# Basisboard_REV0100.net
KiCad netlist of a schematic drawn in EAGLE
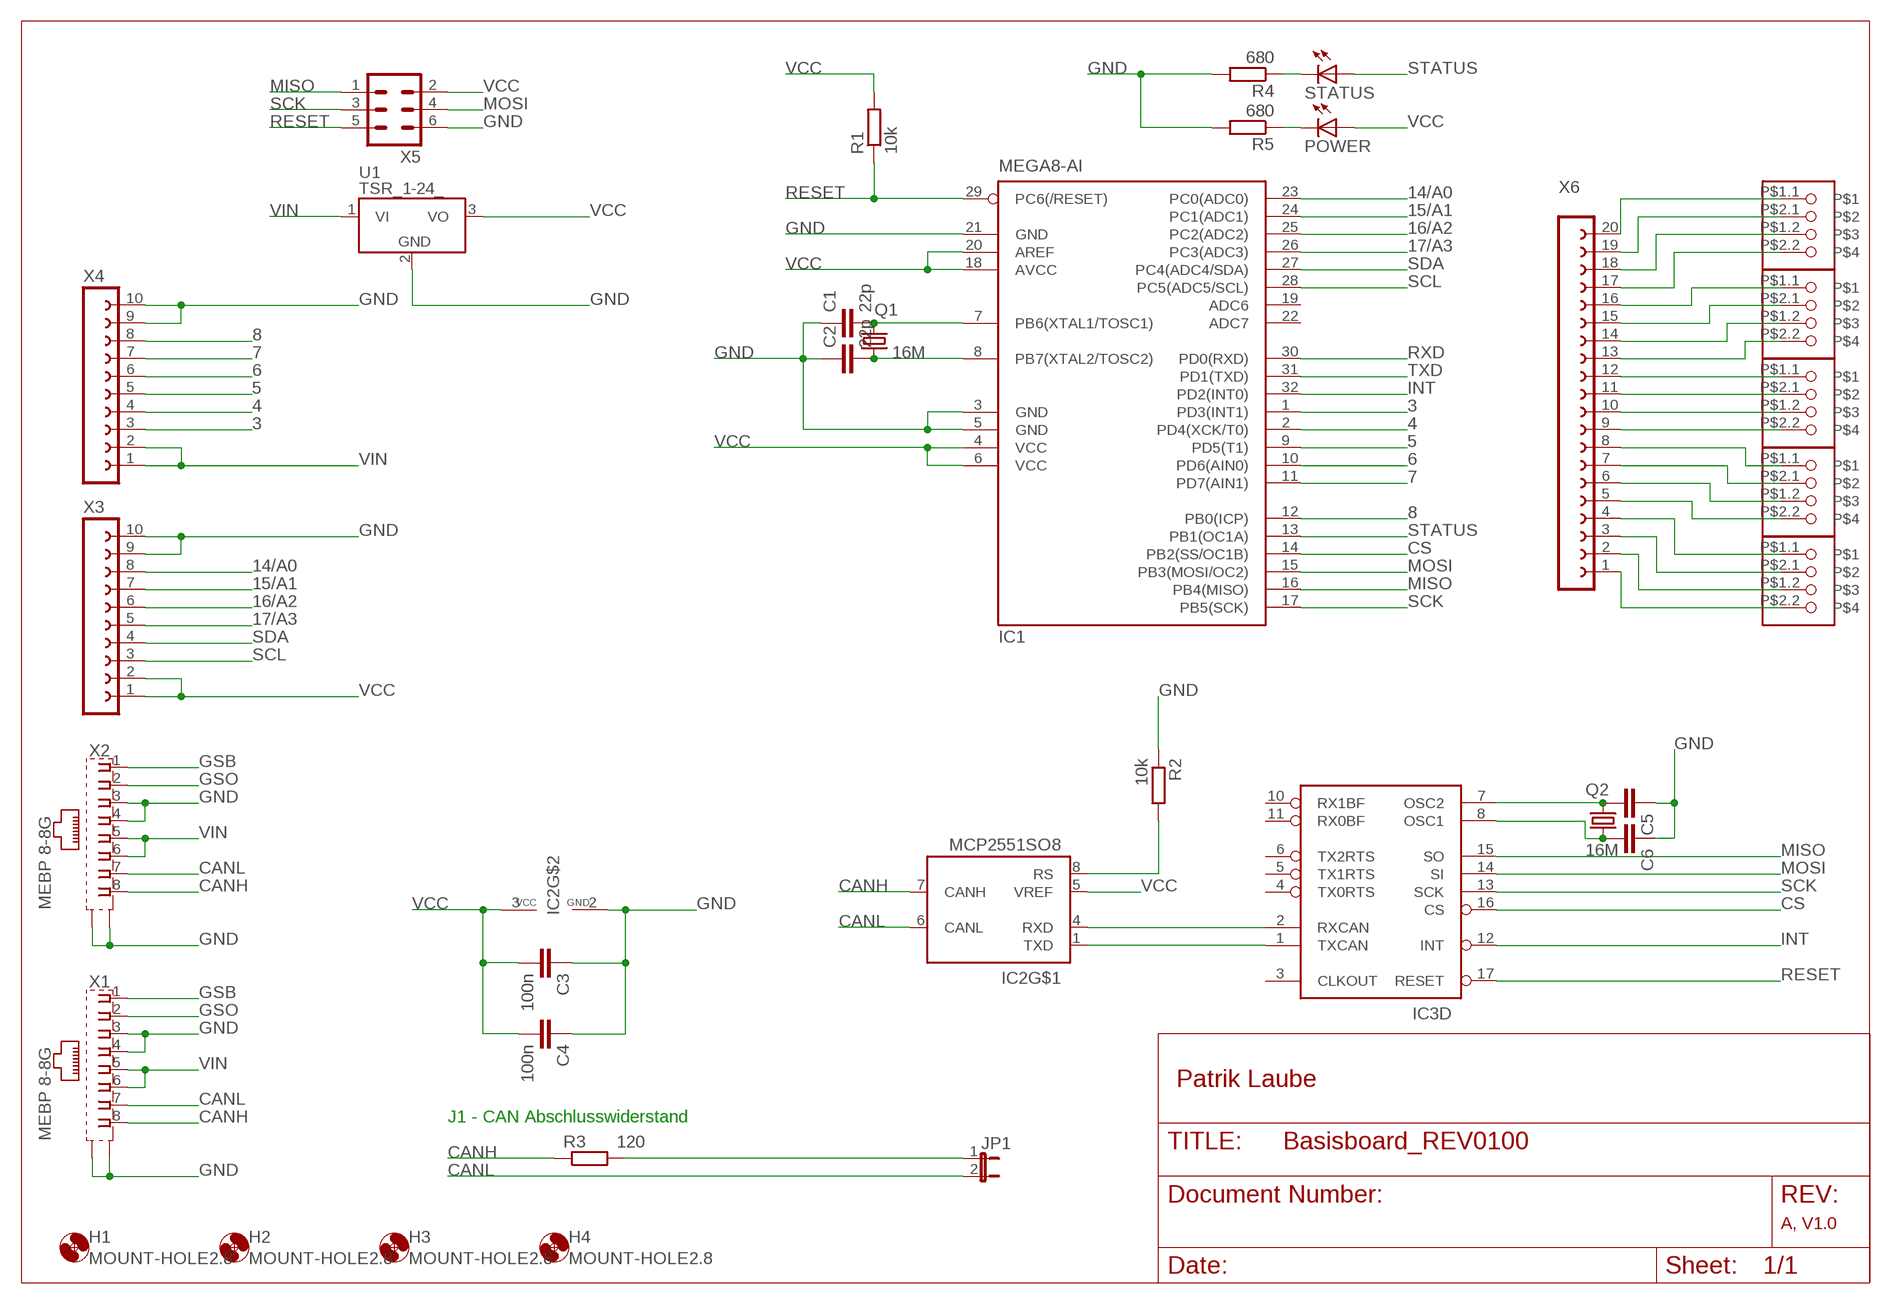
[diagram p0: schematic, sheet 1]

(export (version "E")
  (design (tool "Eeschema 10.0.6"))
  (components
    (comp (ref "C1")
      (value "22p")
      (footprint "eagle-import:C1206")
      (libsource (lib "eagle-import") (part "C-EUC1206"))
    )
    (comp (ref "C2")
      (value "22p")
      (footprint "eagle-import:C1206")
      (libsource (lib "eagle-import") (part "C-EUC1206"))
    )
    (comp (ref "C3")
      (value "100n")
      (footprint "eagle-import:C1206")
      (libsource (lib "eagle-import") (part "C-EUC1206"))
    )
    (comp (ref "C4")
      (value "100n")
      (footprint "eagle-import:C1206")
      (libsource (lib "eagle-import") (part "C-EUC1206"))
    )
    (comp (ref "C5")
      (value "C-EUC1206")
      (footprint "eagle-import:C1206")
      (libsource (lib "eagle-import") (part "C-EUC1206"))
    )
    (comp (ref "C6")
      (value "C-EUC1206")
      (footprint "eagle-import:C1206")
      (libsource (lib "eagle-import") (part "C-EUC1206"))
    )
    (comp (ref "H1")
      (value "MOUNT-HOLE2.8")
      (footprint "eagle-import:2,8")
      (libsource (lib "eagle-import") (part "MOUNT-HOLE2.8"))
    )
    (comp (ref "H2")
      (value "MOUNT-HOLE2.8")
      (footprint "eagle-import:2,8")
      (libsource (lib "eagle-import") (part "MOUNT-HOLE2.8"))
    )
    (comp (ref "H3")
      (value "MOUNT-HOLE2.8")
      (footprint "eagle-import:2,8")
      (libsource (lib "eagle-import") (part "MOUNT-HOLE2.8"))
    )
    (comp (ref "H4")
      (value "MOUNT-HOLE2.8")
      (footprint "eagle-import:2,8")
      (libsource (lib "eagle-import") (part "MOUNT-HOLE2.8"))
    )
    (comp (ref "IC1")
      (value "MEGA8-AI")
      (footprint "eagle-import:TQFP32-08")
      (fields (field (name "MPN") "ATMEGA8-16AU"))
      (libsource (lib "eagle-import") (part "MEGA8-AI"))
    )
    (comp (ref "IC2")
      (value "MCP2551SO8")
      (footprint "eagle-import:SO08")
      (libsource (lib "eagle-import") (part "MCP2551SO8"))
    )
    (comp (ref "IC3")
      (value "MCP2515SO")
      (footprint "eagle-import:SO-18W")
      (libsource (lib "eagle-import") (part "MCP2515SO"))
    )
    (comp (ref "JP1")
      (value "JP1E")
      (footprint "eagle-import:JP1")
      (libsource (lib "eagle-import") (part "JP1E"))
    )
    (comp (ref "POWER")
      (value "LEDCHIPLED_1206")
      (footprint "eagle-import:CHIPLED_1206")
      (libsource (lib "eagle-import") (part "LEDCHIPLED_1206"))
    )
    (comp (ref "Q1")
      (value "16M")
      (footprint "eagle-import:HC49_S")
      (libsource (lib "eagle-import") (part "CRYSTALHC49S"))
    )
    (comp (ref "Q2")
      (value "16M")
      (footprint "eagle-import:HC49_S")
      (libsource (lib "eagle-import") (part "CRYSTALHC49S"))
    )
    (comp (ref "R1")
      (value "10k")
      (footprint "eagle-import:R1206")
      (libsource (lib "eagle-import") (part "R-EU_R1206"))
    )
    (comp (ref "R2")
      (value "10k")
      (footprint "eagle-import:R1206")
      (libsource (lib "eagle-import") (part "R-EU_R1206"))
    )
    (comp (ref "R3")
      (value "120")
      (footprint "eagle-import:R1206")
      (libsource (lib "eagle-import") (part "rcl_334_R-EU_R1206"))
    )
    (comp (ref "R4")
      (value "680")
      (footprint "eagle-import:R1206")
      (libsource (lib "eagle-import") (part "R-EU_R1206"))
    )
    (comp (ref "R5")
      (value "680")
      (footprint "eagle-import:R1206")
      (libsource (lib "eagle-import") (part "R-EU_R1206"))
    )
    (comp (ref "STATUS")
      (value "LEDCHIPLED_1206")
      (footprint "eagle-import:CHIPLED_1206")
      (libsource (lib "eagle-import") (part "LEDCHIPLED_1206"))
    )
    (comp (ref "U$4")
      (value "AKL093-06")
      (footprint "eagle-import:AKL093-06")
      (libsource (lib "eagle-import") (part "AKL093-06"))
    )
    (comp (ref "U$5")
      (value "AKL093-06")
      (footprint "eagle-import:AKL093-06")
      (libsource (lib "eagle-import") (part "AKL093-06"))
    )
    (comp (ref "U$6")
      (value "AKL093-06")
      (footprint "eagle-import:AKL093-06")
      (libsource (lib "eagle-import") (part "AKL093-06"))
    )
    (comp (ref "U$7")
      (value "AKL093-06")
      (footprint "eagle-import:AKL093-06")
      (libsource (lib "eagle-import") (part "AKL093-06"))
    )
    (comp (ref "U$8")
      (value "AKL093-06")
      (footprint "eagle-import:AKL093-06")
      (libsource (lib "eagle-import") (part "AKL093-06"))
    )
    (comp (ref "U1")
      (value "TSR_1-24_")
      (footprint "eagle-import:TSR-1")
      (libsource (lib "eagle-import") (part "TSR_1-24_"))
    )
    (comp (ref "X1")
      (value "MEBP 8-8G")
      (footprint "eagle-import:XRJF-01A-0-D2A-010")
      (libsource (lib "eagle-import") (part "XRJFMEBP-8-8G-01A-0-D22-020"))
    )
    (comp (ref "X2")
      (value "MEBP 8-8G")
      (footprint "eagle-import:XRJF-01A-0-D2A-010")
      (libsource (lib "eagle-import") (part "XRJFMEBP-8-8G-01A-0-D22-020"))
    )
    (comp (ref "X3")
      (value "FE10-1")
      (footprint "eagle-import:FE10")
      (libsource (lib "eagle-import") (part "FE10-1"))
    )
    (comp (ref "X4")
      (value "FE10-1")
      (footprint "eagle-import:FE10")
      (libsource (lib "eagle-import") (part "FE10-1"))
    )
    (comp (ref "X5")
      (value "MA03-2")
      (footprint "eagle-import:MA03-2")
      (libsource (lib "eagle-import") (part "MA03-2"))
    )
    (comp (ref "X6")
      (value "FE20-1")
      (footprint "eagle-import:FE20")
      (libsource (lib "eagle-import") (part "FE20-1"))
    )
  )
  (nets
    (net (code "1") (name "/3") (class "Default")
      (node (ref "IC1") (pin "1") (pinfunction "PD3(INT1)_1") (pintype "bidirectional"))
      (node (ref "X4") (pin "3") (pinfunction "3_3") (pintype "passive"))
    )
    (net (code "2") (name "/4") (class "Default")
      (node (ref "IC1") (pin "2") (pinfunction "PD4(XCK/T0)_2") (pintype "bidirectional"))
      (node (ref "X4") (pin "4") (pinfunction "4_4") (pintype "passive"))
    )
    (net (code "3") (name "/5") (class "Default")
      (node (ref "IC1") (pin "9") (pinfunction "PD5(T1)_9") (pintype "bidirectional"))
      (node (ref "X4") (pin "5") (pinfunction "5_5") (pintype "passive"))
    )
    (net (code "4") (name "/6") (class "Default")
      (node (ref "IC1") (pin "10") (pinfunction "PD6(AIN0)_10") (pintype "bidirectional"))
      (node (ref "X4") (pin "6") (pinfunction "6_6") (pintype "passive"))
    )
    (net (code "5") (name "/7") (class "Default")
      (node (ref "IC1") (pin "11") (pinfunction "PD7(AIN1)_11") (pintype "bidirectional"))
      (node (ref "X4") (pin "7") (pinfunction "7_7") (pintype "passive"))
    )
    (net (code "6") (name "/8") (class "Default")
      (node (ref "IC1") (pin "12") (pinfunction "PB0(ICP)_12") (pintype "bidirectional"))
      (node (ref "X4") (pin "8") (pinfunction "8_8") (pintype "passive"))
    )
    (net (code "7") (name "/14{slash}A0") (class "Default")
      (node (ref "IC1") (pin "23") (pinfunction "PC0(ADC0)_23") (pintype "bidirectional"))
      (node (ref "X3") (pin "8") (pinfunction "8_8") (pintype "passive"))
    )
    (net (code "8") (name "/15{slash}A1") (class "Default")
      (node (ref "IC1") (pin "24") (pinfunction "PC1(ADC1)_24") (pintype "bidirectional"))
      (node (ref "X3") (pin "7") (pinfunction "7_7") (pintype "passive"))
    )
    (net (code "9") (name "/16{slash}A2") (class "Default")
      (node (ref "IC1") (pin "25") (pinfunction "PC2(ADC2)_25") (pintype "bidirectional"))
      (node (ref "X3") (pin "6") (pinfunction "6_6") (pintype "passive"))
    )
    (net (code "10") (name "/17{slash}A3") (class "Default")
      (node (ref "IC1") (pin "26") (pinfunction "PC3(ADC3)_26") (pintype "bidirectional"))
      (node (ref "X3") (pin "5") (pinfunction "5_5") (pintype "passive"))
    )
    (net (code "11") (name "/CANH") (class "Default")
      (node (ref "IC2") (pin "7") (pinfunction "CANH_7") (pintype "bidirectional"))
      (node (ref "R3") (pin "1") (pinfunction "1_1") (pintype "passive"))
      (node (ref "X1") (pin "8") (pinfunction "8_8") (pintype "passive"))
      (node (ref "X2") (pin "8") (pinfunction "8_8") (pintype "passive"))
    )
    (net (code "12") (name "/CANL") (class "Default")
      (node (ref "IC2") (pin "6") (pinfunction "CANL_6") (pintype "bidirectional"))
      (node (ref "JP1") (pin "2") (pinfunction "2_2") (pintype "passive"))
      (node (ref "X1") (pin "7") (pinfunction "7_7") (pintype "passive"))
      (node (ref "X2") (pin "7") (pinfunction "7_7") (pintype "passive"))
    )
    (net (code "13") (name "/CS") (class "Default")
      (node (ref "IC1") (pin "14") (pinfunction "PB2(SS/OC1B)_14") (pintype "bidirectional"))
      (node (ref "IC3") (pin "16") (pinfunction "CS_16") (pintype "input"))
    )
    (net (code "14") (name "/GND") (class "Default")
      (node (ref "C1") (pin "1") (pinfunction "1_1") (pintype "passive"))
      (node (ref "C2") (pin "1") (pinfunction "1_1") (pintype "passive"))
      (node (ref "C3") (pin "1") (pinfunction "1_1") (pintype "passive"))
      (node (ref "C4") (pin "1") (pinfunction "1_1") (pintype "passive"))
      (node (ref "C5") (pin "1") (pinfunction "1_1") (pintype "passive"))
      (node (ref "C6") (pin "1") (pinfunction "1_1") (pintype "passive"))
      (node (ref "IC1") (pin "21") (pinfunction "GND_21") (pintype "power_in"))
      (node (ref "IC1") (pin "3") (pinfunction "GND_3") (pintype "power_in"))
      (node (ref "IC1") (pin "5") (pinfunction "GND_5") (pintype "power_in"))
      (node (ref "IC2") (pin "2") (pinfunction "GND_2") (pintype "power_in"))
      (node (ref "R2") (pin "1") (pinfunction "1_1") (pintype "passive"))
      (node (ref "R4") (pin "2") (pinfunction "2_2") (pintype "passive"))
      (node (ref "R5") (pin "2") (pinfunction "2_2") (pintype "passive"))
      (node (ref "U1") (pin "2") (pinfunction "GND_2") (pintype "power_in"))
      (node (ref "X1") (pin "3") (pinfunction "3_3") (pintype "passive"))
      (node (ref "X1") (pin "4") (pinfunction "4_4") (pintype "passive"))
      (node (ref "X1") (pin "S1") (pinfunction "S_S1") (pintype "passive"))
      (node (ref "X1") (pin "S2") (pinfunction "S_S2") (pintype "passive"))
      (node (ref "X2") (pin "3") (pinfunction "3_3") (pintype "passive"))
      (node (ref "X2") (pin "4") (pinfunction "4_4") (pintype "passive"))
      (node (ref "X2") (pin "S1") (pinfunction "S_S1") (pintype "passive"))
      (node (ref "X2") (pin "S2") (pinfunction "S_S2") (pintype "passive"))
      (node (ref "X3") (pin "10") (pinfunction "10_10") (pintype "passive"))
      (node (ref "X3") (pin "9") (pinfunction "9_9") (pintype "passive"))
      (node (ref "X4") (pin "10") (pinfunction "10_10") (pintype "passive"))
      (node (ref "X4") (pin "9") (pinfunction "9_9") (pintype "passive"))
      (node (ref "X5") (pin "6") (pinfunction "6_6") (pintype "passive"))
    )
    (net (code "15") (name "/GSB") (class "Default")
      (node (ref "X1") (pin "1") (pinfunction "1_1") (pintype "passive"))
      (node (ref "X2") (pin "1") (pinfunction "1_1") (pintype "passive"))
    )
    (net (code "16") (name "/GSO") (class "Default")
      (node (ref "X1") (pin "2") (pinfunction "2_2") (pintype "passive"))
      (node (ref "X2") (pin "2") (pinfunction "2_2") (pintype "passive"))
    )
    (net (code "17") (name "/INT") (class "Default")
      (node (ref "IC1") (pin "32") (pinfunction "PD2(INT0)_32") (pintype "bidirectional"))
      (node (ref "IC3") (pin "12") (pinfunction "INT_12") (pintype "output"))
    )
    (net (code "18") (name "/MISO") (class "Default")
      (node (ref "IC1") (pin "16") (pinfunction "PB4(MISO)_16") (pintype "bidirectional"))
      (node (ref "IC3") (pin "15") (pinfunction "SO_15") (pintype "output"))
      (node (ref "X5") (pin "1") (pinfunction "1_1") (pintype "passive"))
    )
    (net (code "19") (name "/MOSI") (class "Default")
      (node (ref "IC1") (pin "15") (pinfunction "PB3(MOSI/OC2)_15") (pintype "bidirectional"))
      (node (ref "IC3") (pin "14") (pinfunction "SI_14") (pintype "input"))
      (node (ref "X5") (pin "4") (pinfunction "4_4") (pintype "passive"))
    )
    (net (code "20") (name "/RESET") (class "Default")
      (node (ref "IC1") (pin "29") (pinfunction "PC6(/RESET)_29") (pintype "bidirectional"))
      (node (ref "IC3") (pin "17") (pinfunction "RESET_17") (pintype "input"))
      (node (ref "R1") (pin "1") (pinfunction "1_1") (pintype "passive"))
      (node (ref "X5") (pin "5") (pinfunction "5_5") (pintype "passive"))
    )
    (net (code "21") (name "/RXD") (class "Default")
      (node (ref "IC1") (pin "30") (pinfunction "PD0(RXD)_30") (pintype "bidirectional"))
    )
    (net (code "22") (name "/SCK") (class "Default")
      (node (ref "IC1") (pin "17") (pinfunction "PB5(SCK)_17") (pintype "bidirectional"))
      (node (ref "IC3") (pin "13") (pinfunction "SCK_13") (pintype "input"))
      (node (ref "X5") (pin "3") (pinfunction "3_3") (pintype "passive"))
    )
    (net (code "23") (name "/SCL") (class "Default")
      (node (ref "IC1") (pin "28") (pinfunction "PC5(ADC5/SCL)_28") (pintype "bidirectional"))
      (node (ref "X3") (pin "3") (pinfunction "3_3") (pintype "passive"))
    )
    (net (code "24") (name "/SDA") (class "Default")
      (node (ref "IC1") (pin "27") (pinfunction "PC4(ADC4/SDA)_27") (pintype "bidirectional"))
      (node (ref "X3") (pin "4") (pinfunction "4_4") (pintype "passive"))
    )
    (net (code "25") (name "/STATUS") (class "Default")
      (node (ref "IC1") (pin "13") (pinfunction "PB1(OC1A)_13") (pintype "bidirectional"))
      (node (ref "STATUS") (pin "A") (pinfunction "A_A") (pintype "passive"))
    )
    (net (code "26") (name "/TXD") (class "Default")
      (node (ref "IC1") (pin "31") (pinfunction "PD1(TXD)_31") (pintype "bidirectional"))
    )
    (net (code "27") (name "/VCC") (class "Default")
      (node (ref "C3") (pin "2") (pinfunction "2_2") (pintype "passive"))
      (node (ref "C4") (pin "2") (pinfunction "2_2") (pintype "passive"))
      (node (ref "IC1") (pin "18") (pinfunction "AVCC_18") (pintype "power_in"))
      (node (ref "IC1") (pin "20") (pinfunction "AREF_20") (pintype "passive"))
      (node (ref "IC1") (pin "4") (pinfunction "VCC_4") (pintype "power_in"))
      (node (ref "IC1") (pin "6") (pinfunction "VCC_6") (pintype "power_in"))
      (node (ref "IC2") (pin "3") (pinfunction "VCC_3") (pintype "power_in"))
      (node (ref "IC2") (pin "5") (pinfunction "VREF_5") (pintype "bidirectional"))
      (node (ref "POWER") (pin "A") (pinfunction "A_A") (pintype "passive"))
      (node (ref "R1") (pin "2") (pinfunction "2_2") (pintype "passive"))
      (node (ref "U1") (pin "3") (pinfunction "VO_3") (pintype "power_in"))
      (node (ref "X3") (pin "1") (pinfunction "1_1") (pintype "passive"))
      (node (ref "X3") (pin "2") (pinfunction "2_2") (pintype "passive"))
      (node (ref "X5") (pin "2") (pinfunction "2_2") (pintype "passive"))
    )
    (net (code "28") (name "/VIN") (class "Default")
      (node (ref "U1") (pin "1") (pinfunction "VI_1") (pintype "power_in"))
      (node (ref "X1") (pin "5") (pinfunction "5_5") (pintype "passive"))
      (node (ref "X1") (pin "6") (pinfunction "6_6") (pintype "passive"))
      (node (ref "X2") (pin "5") (pinfunction "5_5") (pintype "passive"))
      (node (ref "X2") (pin "6") (pinfunction "6_6") (pintype "passive"))
      (node (ref "X4") (pin "1") (pinfunction "1_1") (pintype "passive"))
      (node (ref "X4") (pin "2") (pinfunction "2_2") (pintype "passive"))
    )
    (net (code "29") (name "Net-(IC1-PB6(XTAL1{slash}TOSC1))") (class "Default")
      (node (ref "C1") (pin "2") (pinfunction "2_2") (pintype "passive"))
      (node (ref "IC1") (pin "7") (pinfunction "PB6(XTAL1/TOSC1)_7") (pintype "bidirectional"))
      (node (ref "Q1") (pin "2") (pinfunction "2_2") (pintype "passive"))
    )
    (net (code "30") (name "Net-(IC1-PB7(XTAL2{slash}TOSC2))") (class "Default")
      (node (ref "C2") (pin "2") (pinfunction "2_2") (pintype "passive"))
      (node (ref "IC1") (pin "8") (pinfunction "PB7(XTAL2/TOSC2)_8") (pintype "bidirectional"))
      (node (ref "Q1") (pin "1") (pinfunction "1_1") (pintype "passive"))
    )
    (net (code "31") (name "Net-(IC2A-RS)") (class "Default")
      (node (ref "IC2") (pin "8") (pinfunction "RS_8") (pintype "bidirectional"))
      (node (ref "R2") (pin "2") (pinfunction "2_2") (pintype "passive"))
    )
    (net (code "32") (name "Net-(IC2A-RXD)") (class "Default")
      (node (ref "IC2") (pin "4") (pinfunction "RXD_4") (pintype "bidirectional"))
      (node (ref "IC3") (pin "2") (pinfunction "RXCAN_2") (pintype "input"))
    )
    (net (code "33") (name "Net-(IC2A-TXD)") (class "Default")
      (node (ref "IC2") (pin "1") (pinfunction "TXD_1") (pintype "bidirectional"))
      (node (ref "IC3") (pin "1") (pinfunction "TXCAN_1") (pintype "output"))
    )
    (net (code "34") (name "Net-(IC3A-OSC1)") (class "Default")
      (node (ref "C6") (pin "2") (pinfunction "2_2") (pintype "passive"))
      (node (ref "IC3") (pin "8") (pinfunction "OSC1_8") (pintype "input"))
      (node (ref "Q2") (pin "2") (pinfunction "2_2") (pintype "passive"))
    )
    (net (code "35") (name "Net-(IC3A-OSC2)") (class "Default")
      (node (ref "C5") (pin "2") (pinfunction "2_2") (pintype "passive"))
      (node (ref "IC3") (pin "7") (pinfunction "OSC2_7") (pintype "input"))
      (node (ref "Q2") (pin "1") (pinfunction "1_1") (pintype "passive"))
    )
    (net (code "36") (name "Net-(JP1-Pad1)") (class "Default")
      (node (ref "JP1") (pin "1") (pinfunction "1_1") (pintype "passive"))
      (node (ref "R3") (pin "2") (pinfunction "2_2") (pintype "passive"))
    )
    (net (code "37") (name "Net-(POWER-PadC)") (class "Default")
      (node (ref "POWER") (pin "C") (pinfunction "C_C") (pintype "passive"))
      (node (ref "R5") (pin "1") (pinfunction "1_1") (pintype "passive"))
    )
    (net (code "38") (name "Net-(R4-Pad1)") (class "Default")
      (node (ref "R4") (pin "1") (pinfunction "1_1") (pintype "passive"))
      (node (ref "STATUS") (pin "C") (pinfunction "C_C") (pintype "passive"))
    )
    (net (code "39") (name "Net-(U$4-P$1)") (class "Default")
      (node (ref "U$4") (pin "P$1.1") (pinfunction "P$1_P$1.1") (pintype "bidirectional"))
      (node (ref "X6") (pin "12") (pinfunction "12_12") (pintype "passive"))
    )
    (net (code "40") (name "Net-(U$4-P$2)") (class "Default")
      (node (ref "U$4") (pin "P$2.1") (pinfunction "P$2_P$2.1") (pintype "bidirectional"))
      (node (ref "X6") (pin "11") (pinfunction "11_11") (pintype "passive"))
    )
    (net (code "41") (name "Net-(U$4-P$3)") (class "Default")
      (node (ref "U$4") (pin "P$1.2") (pinfunction "P$3_P$1.2") (pintype "bidirectional"))
      (node (ref "X6") (pin "10") (pinfunction "10_10") (pintype "passive"))
    )
    (net (code "42") (name "Net-(U$4-P$4)") (class "Default")
      (node (ref "U$4") (pin "P$2.2") (pinfunction "P$4_P$2.2") (pintype "bidirectional"))
      (node (ref "X6") (pin "9") (pinfunction "9_9") (pintype "passive"))
    )
    (net (code "43") (name "Net-(U$5-P$1)") (class "Default")
      (node (ref "U$5") (pin "P$1.1") (pinfunction "P$1_P$1.1") (pintype "bidirectional"))
      (node (ref "X6") (pin "16") (pinfunction "16_16") (pintype "passive"))
    )
    (net (code "44") (name "Net-(U$5-P$2)") (class "Default")
      (node (ref "U$5") (pin "P$2.1") (pinfunction "P$2_P$2.1") (pintype "bidirectional"))
      (node (ref "X6") (pin "15") (pinfunction "15_15") (pintype "passive"))
    )
    (net (code "45") (name "Net-(U$5-P$3)") (class "Default")
      (node (ref "U$5") (pin "P$1.2") (pinfunction "P$3_P$1.2") (pintype "bidirectional"))
      (node (ref "X6") (pin "14") (pinfunction "14_14") (pintype "passive"))
    )
    (net (code "46") (name "Net-(U$5-P$4)") (class "Default")
      (node (ref "U$5") (pin "P$2.2") (pinfunction "P$4_P$2.2") (pintype "bidirectional"))
      (node (ref "X6") (pin "13") (pinfunction "13_13") (pintype "passive"))
    )
    (net (code "47") (name "Net-(U$6-P$1)") (class "Default")
      (node (ref "U$6") (pin "P$1.1") (pinfunction "P$1_P$1.1") (pintype "bidirectional"))
      (node (ref "X6") (pin "8") (pinfunction "8_8") (pintype "passive"))
    )
    (net (code "48") (name "Net-(U$6-P$2)") (class "Default")
      (node (ref "U$6") (pin "P$2.1") (pinfunction "P$2_P$2.1") (pintype "bidirectional"))
      (node (ref "X6") (pin "7") (pinfunction "7_7") (pintype "passive"))
    )
    (net (code "49") (name "Net-(U$6-P$3)") (class "Default")
      (node (ref "U$6") (pin "P$1.2") (pinfunction "P$3_P$1.2") (pintype "bidirectional"))
      (node (ref "X6") (pin "6") (pinfunction "6_6") (pintype "passive"))
    )
    (net (code "50") (name "Net-(U$6-P$4)") (class "Default")
      (node (ref "U$6") (pin "P$2.2") (pinfunction "P$4_P$2.2") (pintype "bidirectional"))
      (node (ref "X6") (pin "5") (pinfunction "5_5") (pintype "passive"))
    )
    (net (code "51") (name "Net-(U$7-P$1)") (class "Default")
      (node (ref "U$7") (pin "P$1.1") (pinfunction "P$1_P$1.1") (pintype "bidirectional"))
      (node (ref "X6") (pin "4") (pinfunction "4_4") (pintype "passive"))
    )
    (net (code "52") (name "Net-(U$7-P$2)") (class "Default")
      (node (ref "U$7") (pin "P$2.1") (pinfunction "P$2_P$2.1") (pintype "bidirectional"))
      (node (ref "X6") (pin "3") (pinfunction "3_3") (pintype "passive"))
    )
    (net (code "53") (name "Net-(U$7-P$3)") (class "Default")
      (node (ref "U$7") (pin "P$1.2") (pinfunction "P$3_P$1.2") (pintype "bidirectional"))
      (node (ref "X6") (pin "2") (pinfunction "2_2") (pintype "passive"))
    )
    (net (code "54") (name "Net-(U$7-P$4)") (class "Default")
      (node (ref "U$7") (pin "P$2.2") (pinfunction "P$4_P$2.2") (pintype "bidirectional"))
      (node (ref "X6") (pin "1") (pinfunction "1_1") (pintype "passive"))
    )
    (net (code "55") (name "Net-(U$8-P$1)") (class "Default")
      (node (ref "U$8") (pin "P$1.1") (pinfunction "P$1_P$1.1") (pintype "bidirectional"))
      (node (ref "X6") (pin "20") (pinfunction "20_20") (pintype "passive"))
    )
    (net (code "56") (name "Net-(U$8-P$2)") (class "Default")
      (node (ref "U$8") (pin "P$2.1") (pinfunction "P$2_P$2.1") (pintype "bidirectional"))
      (node (ref "X6") (pin "19") (pinfunction "19_19") (pintype "passive"))
    )
    (net (code "57") (name "Net-(U$8-P$3)") (class "Default")
      (node (ref "U$8") (pin "P$1.2") (pinfunction "P$3_P$1.2") (pintype "bidirectional"))
      (node (ref "X6") (pin "18") (pinfunction "18_18") (pintype "passive"))
    )
    (net (code "58") (name "Net-(U$8-P$4)") (class "Default")
      (node (ref "U$8") (pin "P$2.2") (pinfunction "P$4_P$2.2") (pintype "bidirectional"))
      (node (ref "X6") (pin "17") (pinfunction "17_17") (pintype "passive"))
    )
    (net (code "59") (name "unconnected-(IC1-ADC6-Pad19)") (class "Default")
      (node (ref "IC1") (pin "19") (pinfunction "ADC6_19") (pintype "bidirectional"))
    )
    (net (code "60") (name "unconnected-(IC1-ADC7-Pad22)") (class "Default")
      (node (ref "IC1") (pin "22") (pinfunction "ADC7_22") (pintype "bidirectional"))
    )
    (net (code "61") (name "unconnected-(IC3A-CLKOUT-Pad3)") (class "Default")
      (node (ref "IC3") (pin "3") (pinfunction "CLKOUT_3") (pintype "output"))
    )
    (net (code "62") (name "unconnected-(IC3A-RX0BF-Pad11)") (class "Default")
      (node (ref "IC3") (pin "11") (pinfunction "RX0BF_11") (pintype "output"))
    )
    (net (code "63") (name "unconnected-(IC3A-RX1BF-Pad10)") (class "Default")
      (node (ref "IC3") (pin "10") (pinfunction "RX1BF_10") (pintype "output"))
    )
    (net (code "64") (name "unconnected-(IC3A-TX0RTS-Pad4)") (class "Default")
      (node (ref "IC3") (pin "4") (pinfunction "TX0RTS_4") (pintype "input"))
    )
    (net (code "65") (name "unconnected-(IC3A-TX1RTS-Pad5)") (class "Default")
      (node (ref "IC3") (pin "5") (pinfunction "TX1RTS_5") (pintype "input"))
    )
    (net (code "66") (name "unconnected-(IC3A-TX2RTS-Pad6)") (class "Default")
      (node (ref "IC3") (pin "6") (pinfunction "TX2RTS_6") (pintype "input"))
    )
  )
)
